# Schematic.net
KiCad netlist of a schematic drawn in EAGLE
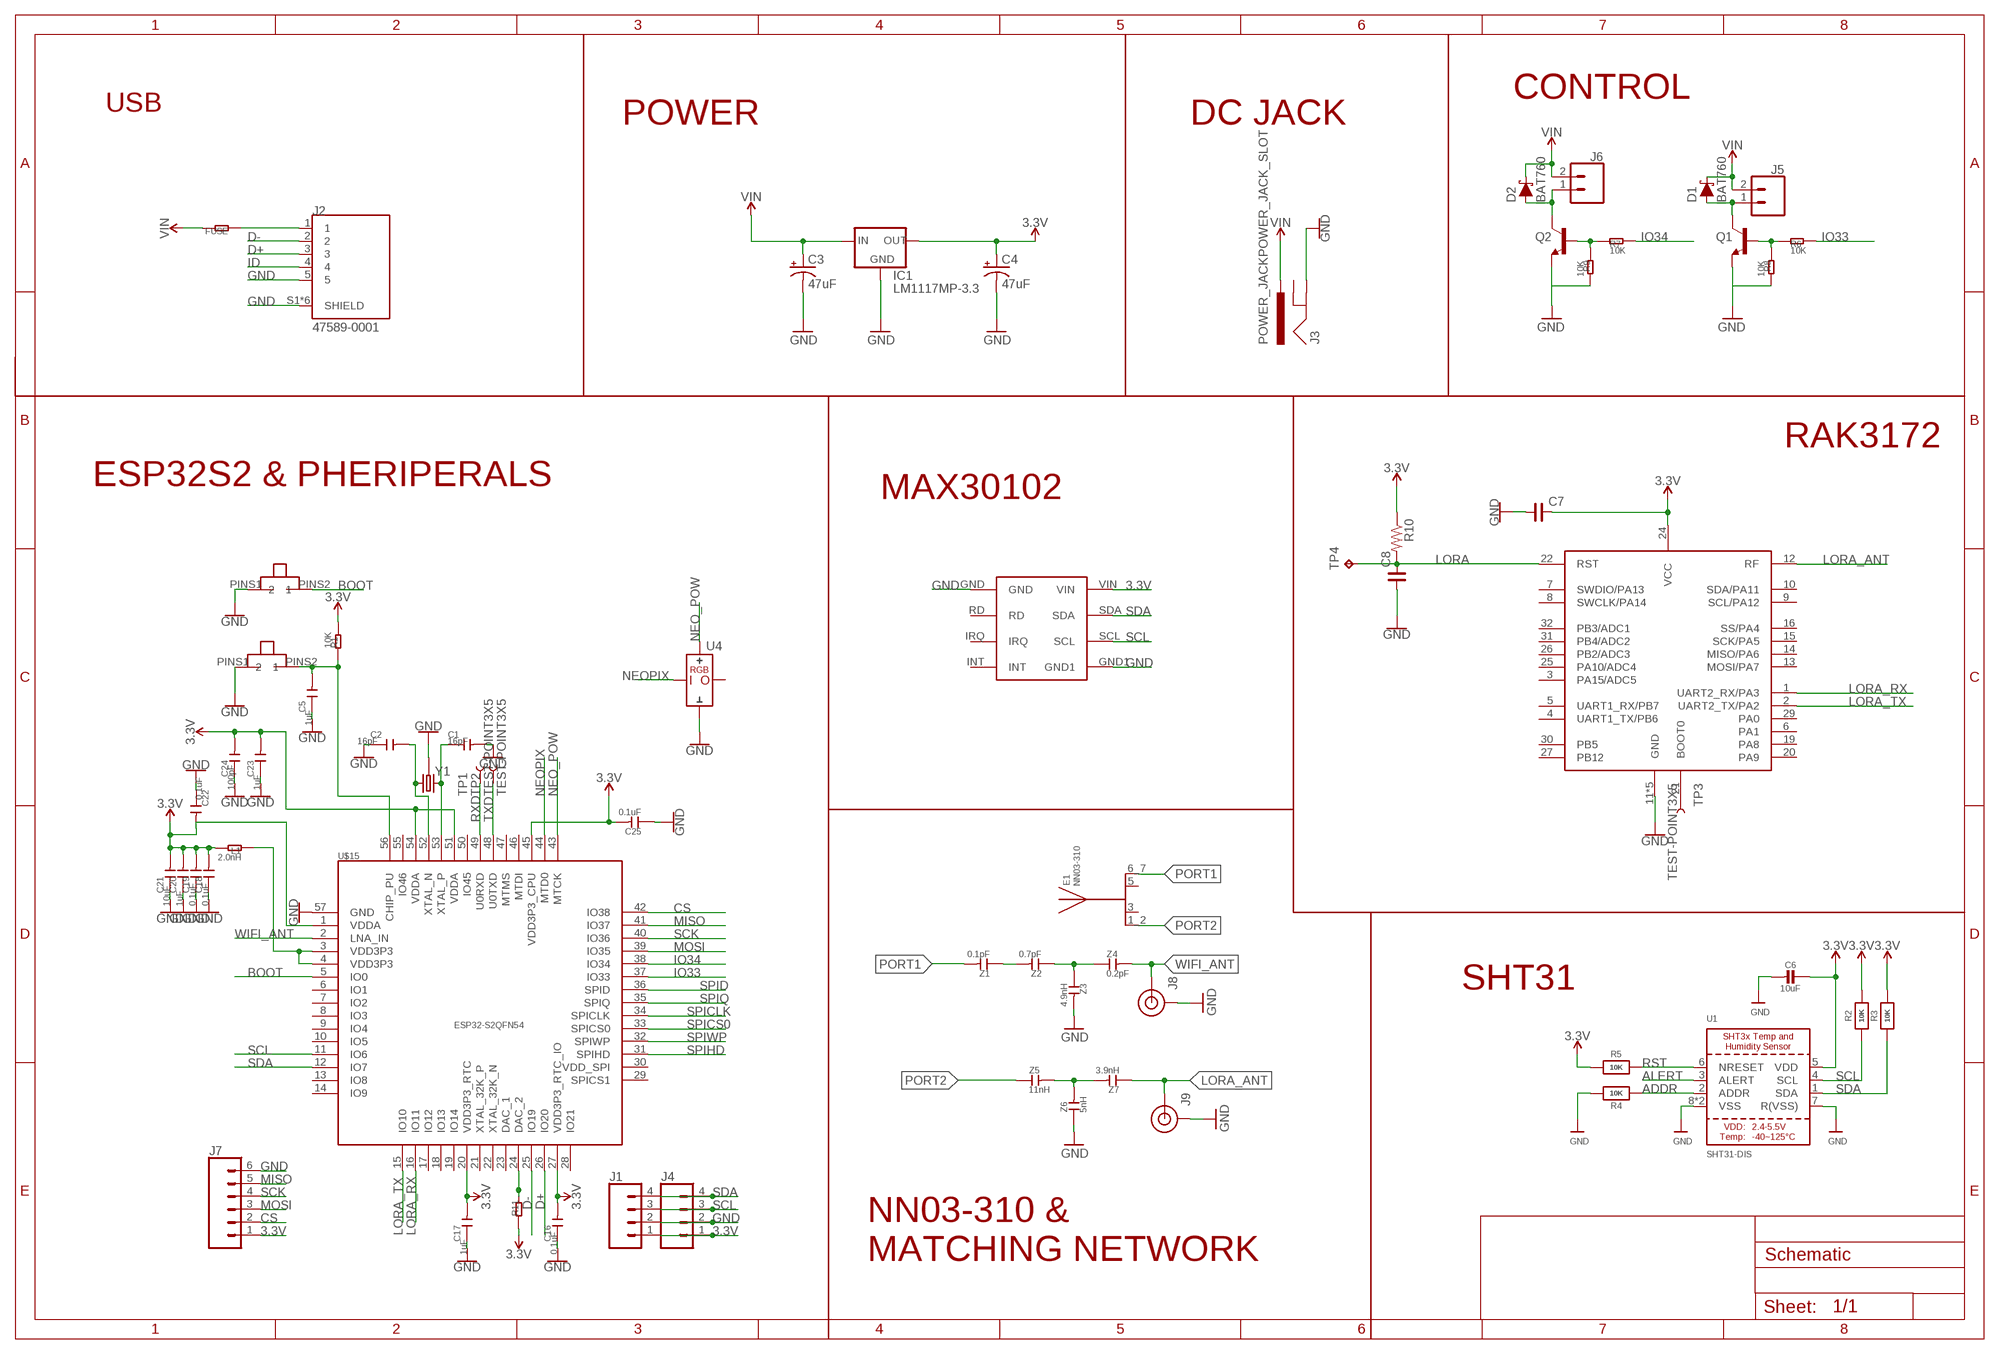
[diagram p0: schematic, sheet 1]

(export (version "E")
  (design (tool "Eeschema 10.0.6"))
  (components
    (comp (ref "C1")
      (value "16pF")
      (footprint "eagle-import:C0603")
      (libsource (lib "eagle-import") (part "CAP-0603"))
    )
    (comp (ref "C2")
      (value "16pF")
      (footprint "eagle-import:C0603")
      (libsource (lib "eagle-import") (part "CAP-0603"))
    )
    (comp (ref "C3")
      (value "47uF")
      (footprint "eagle-import:EIA3216")
      (libsource (lib "eagle-import") (part "10UF-TANT"))
    )
    (comp (ref "C4")
      (value "47uF")
      (footprint "eagle-import:EIA3216")
      (libsource (lib "eagle-import") (part "10UF-TANT"))
    )
    (comp (ref "C5")
      (value "1uF")
      (footprint "eagle-import:C0603")
      (libsource (lib "eagle-import") (part "CAP-0603"))
    )
    (comp (ref "C6")
      (value "10uF")
      (footprint "eagle-import:0805-NO")
      (libsource (lib "eagle-import") (part "CAP_CERAMIC0805-NOOUTLINE"))
    )
    (comp (ref "C7")
      (value "C_0805")
      (footprint "eagle-import:C0805")
      (libsource (lib "eagle-import") (part "C_0805"))
    )
    (comp (ref "C8")
      (value "C_0805")
      (footprint "eagle-import:C0805")
      (libsource (lib "eagle-import") (part "C_0805"))
    )
    (comp (ref "C16")
      (value "0.1uF")
      (footprint "eagle-import:C0603")
      (libsource (lib "eagle-import") (part "CAP-0603"))
    )
    (comp (ref "C17")
      (value "1uF")
      (footprint "eagle-import:C0603")
      (libsource (lib "eagle-import") (part "CAP-0603"))
    )
    (comp (ref "C18")
      (value "0.1uF")
      (footprint "eagle-import:C0603")
      (libsource (lib "eagle-import") (part "CAP-0603"))
    )
    (comp (ref "C19")
      (value "0.1uF")
      (footprint "eagle-import:C0603")
      (libsource (lib "eagle-import") (part "CAP-0603"))
    )
    (comp (ref "C20")
      (value "1uF")
      (footprint "eagle-import:C0603")
      (libsource (lib "eagle-import") (part "CAP-0603"))
    )
    (comp (ref "C21")
      (value "10uF")
      (footprint "eagle-import:C0603")
      (libsource (lib "eagle-import") (part "CAP-0603"))
    )
    (comp (ref "C22")
      (value "0.1uF")
      (footprint "eagle-import:C0603")
      (libsource (lib "eagle-import") (part "CAP-0603"))
    )
    (comp (ref "C23")
      (value "1uF")
      (footprint "eagle-import:C0603")
      (libsource (lib "eagle-import") (part "CAP-0603"))
    )
    (comp (ref "C24")
      (value "100pF")
      (footprint "eagle-import:C0603")
      (libsource (lib "eagle-import") (part "CAP-0603"))
    )
    (comp (ref "C25")
      (value "0.1uF")
      (footprint "eagle-import:C0603")
      (libsource (lib "eagle-import") (part "CAP-0603"))
    )
    (comp (ref "D1")
      (value "BAT760")
      (footprint "eagle-import:SOD-323")
      (libsource (lib "eagle-import") (part "DIODE-SCHOTTKY-BAT60A"))
    )
    (comp (ref "D2")
      (value "BAT760")
      (footprint "eagle-import:SOD-323")
      (libsource (lib "eagle-import") (part "DIODE-SCHOTTKY-BAT60A"))
    )
    (comp (ref "E1")
      (value "NN03-310")
      (footprint "eagle-import:XCVR_NN03-310")
      (fields (field (name "MF") "Ignion"))
      (libsource (lib "eagle-import") (part "NN03-310"))
    )
    (comp (ref "FUSE")
      (value "2.0K")
      (footprint "eagle-import:R0603")
      (libsource (lib "eagle-import") (part "RES-0603"))
    )
    (comp (ref "IC1")
      (value "LM1117MP-3.3")
      (footprint "eagle-import:SOT223")
      (fields (field (name "MF") "Texas Instruments"))
      (libsource (lib "eagle-import") (part "LM1117?-MP3.3"))
    )
    (comp (ref "J1")
      (value "CONN_041X04_NO_SILK")
      (footprint "eagle-import:1X04_NO_SILK")
      (libsource (lib "eagle-import") (part "CONN_041X04_NO_SILK"))
    )
    (comp (ref "J2")
      (value "47589-0001")
      (footprint "eagle-import:MOLEX_47589-0001")
      (fields (field (name "MF") "Molex"))
      (libsource (lib "eagle-import") (part "47589-0001"))
    )
    (comp (ref "J3")
      (value "POWER_JACKPOWER_JACK_SLOT")
      (footprint "eagle-import:POWER_JACK_PTH_SLOT")
      (libsource (lib "eagle-import") (part "POWER_JACKPOWER_JACK_SLOT"))
    )
    (comp (ref "J4")
      (value "CONN_041X04_NO_SILK")
      (footprint "eagle-import:1X04_NO_SILK")
      (libsource (lib "eagle-import") (part "CONN_041X04_NO_SILK"))
    )
    (comp (ref "J5")
      (value "CONN_021X02_NO_SILK")
      (footprint "eagle-import:1X02_NO_SILK")
      (libsource (lib "eagle-import") (part "CONN_021X02_NO_SILK"))
    )
    (comp (ref "J6")
      (value "CONN_021X02_NO_SILK")
      (footprint "eagle-import:1X02_NO_SILK")
      (libsource (lib "eagle-import") (part "CONN_021X02_NO_SILK"))
    )
    (comp (ref "J7")
      (value "CONN_06NO_SILK_FEMALE_PTH")
      (footprint "eagle-import:1X06_NO_SILK")
      (libsource (lib "eagle-import") (part "CONN_06NO_SILK_FEMALE_PTH"))
    )
    (comp (ref "J8")
      (value "U.FL2PIN-REDUCED-FOOTPRINT")
      (footprint "eagle-import:U.FL_REDUCED_FOOTPRINT")
      (libsource (lib "eagle-import") (part "U.FL2PIN-REDUCED-FOOTPRINT"))
    )
    (comp (ref "J9")
      (value "U.FL2PIN-REDUCED-FOOTPRINT")
      (footprint "eagle-import:U.FL_REDUCED_FOOTPRINT")
      (libsource (lib "eagle-import") (part "U.FL2PIN-REDUCED-FOOTPRINT"))
    )
    (comp (ref "L1")
      (value "2.0nH")
      (footprint "eagle-import:R0603")
      (libsource (lib "eagle-import") (part "RES-0603"))
    )
    (comp (ref "Q1")
      (value "500mA/300V")
      (footprint "eagle-import:SOT23-3")
      (libsource (lib "eagle-import") (part "TRANS_NPN-MMBTA42"))
    )
    (comp (ref "Q2")
      (value "500mA/300V")
      (footprint "eagle-import:SOT23-3")
      (libsource (lib "eagle-import") (part "TRANS_NPN-MMBTA42"))
    )
    (comp (ref "R1")
      (value "10K")
      (footprint "eagle-import:R0603")
      (libsource (lib "eagle-import") (part "RES-0603"))
    )
    (comp (ref "R2")
      (value "10K")
      (footprint "eagle-import:0805-NO")
      (libsource (lib "eagle-import") (part "RESISTOR0805_NOOUTLINE"))
    )
    (comp (ref "R3")
      (value "10K")
      (footprint "eagle-import:0805-NO")
      (libsource (lib "eagle-import") (part "RESISTOR0805_NOOUTLINE"))
    )
    (comp (ref "R4")
      (value "10K")
      (footprint "eagle-import:_0805MP")
      (libsource (lib "eagle-import") (part "RESISTOR_0805MP"))
    )
    (comp (ref "R5")
      (value "10K")
      (footprint "eagle-import:0805-NO")
      (libsource (lib "eagle-import") (part "RESISTOR0805_NOOUTLINE"))
    )
    (comp (ref "R6")
      (value "10K")
      (footprint "eagle-import:R0603")
      (libsource (lib "eagle-import") (part "RES-0603"))
    )
    (comp (ref "R7")
      (value "10K")
      (footprint "eagle-import:R0603")
      (libsource (lib "eagle-import") (part "RES-0603"))
    )
    (comp (ref "R8")
      (value "10K")
      (footprint "eagle-import:R0603")
      (libsource (lib "eagle-import") (part "RES-0603"))
    )
    (comp (ref "R9")
      (value "10K")
      (footprint "eagle-import:R0603")
      (libsource (lib "eagle-import") (part "RES-0603"))
    )
    (comp (ref "R10")
      (value "CRCW08050000Z0EA")
      (footprint "eagle-import:RES_0805")
      (fields
        (field (name "DIGIKEY_PART_NUMBER") "541-0.0ATR-ND")
        (field (name "MANUFACTURER") "Vishay Dale")
        (field (name "CREATED_BY") "PCBLayout.com")
      )
      (libsource (lib "eagle-import") (part "CRCW08050000Z0EA"))
    )
    (comp (ref "R11")
      (value "10K")
      (footprint "eagle-import:R0603")
      (libsource (lib "eagle-import") (part "RES-0603"))
    )
    (comp (ref "TP1")
      (value "TEST-POINT3X5")
      (footprint "eagle-import:PAD.03X.05")
      (libsource (lib "eagle-import") (part "TEST-POINT3X5"))
    )
    (comp (ref "TP2")
      (value "TEST-POINT3X5")
      (footprint "eagle-import:PAD.03X.05")
      (libsource (lib "eagle-import") (part "TEST-POINT3X5"))
    )
    (comp (ref "TP3")
      (value "TEST-POINT3X5")
      (footprint "eagle-import:PAD.03X.05")
      (libsource (lib "eagle-import") (part "TEST-POINT3X5"))
    )
    (comp (ref "TP4")
      (value "TPTP12R")
      (footprint "eagle-import:TP12R")
      (libsource (lib "eagle-import") (part "TPTP12R"))
    )
    (comp (ref "U$1")
      (value "TACTILE")
      (footprint "eagle-import:TACTILE")
      (libsource (lib "eagle-import") (part "TACTILE"))
    )
    (comp (ref "U$2")
      (value "TACTILE")
      (footprint "eagle-import:TACTILE")
      (libsource (lib "eagle-import") (part "TACTILE"))
    )
    (comp (ref "U$3")
      (value "MAX30102_BREAKOUT")
      (footprint "eagle-import:MAX30102")
      (libsource (lib "eagle-import") (part "MAX30102_BREAKOUT"))
    )
    (comp (ref "U$4")
      (value "RAK3172HF")
      (footprint "eagle-import:RAK3172")
      (libsource (lib "eagle-import") (part "RAK3172HF"))
    )
    (comp (ref "U$15")
      (value "ESP32-S2QFN54")
      (footprint "eagle-import:QFN40P700X700X90-57T400N")
      (fields
        (field (name "DIGI-KEY_PART_NUMBER") "1965-ESP32-S2CT-ND")
        (field (name "MF") "Espressif Systems")
        (field (name "MP") "ESP32-S2")
      )
      (libsource (lib "eagle-import") (part "ESP32-S2QFN54"))
    )
    (comp (ref "U1")
      (value "SHT31-DIS")
      (footprint "eagle-import:SHT3X")
      (libsource (lib "eagle-import") (part "SHT3X"))
    )
    (comp (ref "U4")
      (value "LED-ADDRESSABLE16MM")
      (footprint "eagle-import:LED-WS2812B-2020-RING")
      (libsource (lib "eagle-import") (part "LED-ADDRESSABLE16MM"))
    )
    (comp (ref "Y1")
      (value "CRYSTAL-GROUNDEDSMD-3.2X2.5")
      (footprint "eagle-import:CRYSTAL-SMD-3.2X2.5MM")
      (libsource (lib "eagle-import") (part "CRYSTAL-GROUNDEDSMD-3.2X2.5"))
    )
    (comp (ref "Z1")
      (value "0.1pF")
      (footprint "eagle-import:C0603")
      (libsource (lib "eagle-import") (part "CAP-0603"))
    )
    (comp (ref "Z2")
      (value "0.7pF")
      (footprint "eagle-import:C0603")
      (libsource (lib "eagle-import") (part "CAP-0603"))
    )
    (comp (ref "Z3")
      (value "4.9nH")
      (footprint "eagle-import:C0603")
      (libsource (lib "eagle-import") (part "CAP-0603"))
    )
    (comp (ref "Z4")
      (value "0.2pF")
      (footprint "eagle-import:C0603")
      (libsource (lib "eagle-import") (part "CAP-0603"))
    )
    (comp (ref "Z5")
      (value "11nH")
      (footprint "eagle-import:C0603")
      (libsource (lib "eagle-import") (part "CAP-0603"))
    )
    (comp (ref "Z6")
      (value "5nH")
      (footprint "eagle-import:C0603")
      (libsource (lib "eagle-import") (part "CAP-0603"))
    )
    (comp (ref "Z7")
      (value "3.9nH")
      (footprint "eagle-import:C0603")
      (libsource (lib "eagle-import") (part "CAP-0603"))
    )
  )
  (nets
    (net (code "1") (name "/ADDR") (class "Default")
      (node (ref "R4") (pin "1") (pinfunction "1_1") (pintype "passive"))
      (node (ref "U1") (pin "2") (pinfunction "ADDR_2") (pintype "bidirectional"))
    )
    (net (code "2") (name "/ALERT") (class "Default")
      (node (ref "U1") (pin "3") (pinfunction "ALERT_3") (pintype "bidirectional"))
    )
    (net (code "3") (name "/BOOT") (class "Default")
      (node (ref "U$15") (pin "5") (pinfunction "IO0_5") (pintype "bidirectional"))
      (node (ref "U$2") (pin "PINS2") (pinfunction "2_PINS2") (pintype "bidirectional"))
    )
    (net (code "4") (name "/CS") (class "Default")
      (node (ref "J7") (pin "2") (pinfunction "2_2") (pintype "passive"))
      (node (ref "U$15") (pin "42") (pinfunction "IO38_42") (pintype "bidirectional"))
    )
    (net (code "5") (name "/D+") (class "Default")
      (node (ref "J2") (pin "3") (pinfunction "3_3") (pintype "passive"))
      (node (ref "U$15") (pin "26") (pinfunction "IO20_26") (pintype "bidirectional"))
    )
    (net (code "6") (name "/D-") (class "Default")
      (node (ref "J2") (pin "2") (pinfunction "2_2") (pintype "passive"))
      (node (ref "U$15") (pin "25") (pinfunction "IO19_25") (pintype "bidirectional"))
    )
    (net (code "7") (name "/ID") (class "Default")
      (node (ref "J2") (pin "4") (pinfunction "4_4") (pintype "passive"))
    )
    (net (code "8") (name "/IO33") (class "Default")
      (node (ref "R6") (pin "2") (pinfunction "2_2") (pintype "passive"))
      (node (ref "U$15") (pin "37") (pinfunction "IO33_37") (pintype "bidirectional"))
    )
    (net (code "9") (name "/IO34") (class "Default")
      (node (ref "R7") (pin "2") (pinfunction "2_2") (pintype "passive"))
      (node (ref "U$15") (pin "38") (pinfunction "IO34_38") (pintype "bidirectional"))
    )
    (net (code "10") (name "/LORA") (class "Default")
      (node (ref "C8") (pin "2") (pinfunction "2_2") (pintype "passive"))
      (node (ref "R10") (pin "2") (pinfunction "2_2") (pintype "passive"))
      (node (ref "TP4") (pin "TP") (pinfunction "TP_TP") (pintype "input"))
      (node (ref "U$4") (pin "22") (pinfunction "RST_22") (pintype "input"))
    )
    (net (code "11") (name "/LORA_RX") (class "Default")
      (node (ref "U$15") (pin "16") (pinfunction "IO11_16") (pintype "bidirectional"))
      (node (ref "U$4") (pin "1") (pinfunction "UART2_RX/PA3_1") (pintype "bidirectional"))
    )
    (net (code "12") (name "/LORA_TX") (class "Default")
      (node (ref "U$15") (pin "15") (pinfunction "IO10_15") (pintype "bidirectional"))
      (node (ref "U$4") (pin "2") (pinfunction "UART2_TX/PA2_2") (pintype "bidirectional"))
    )
    (net (code "13") (name "/MISO") (class "Default")
      (node (ref "J7") (pin "5") (pinfunction "5_5") (pintype "passive"))
      (node (ref "U$15") (pin "41") (pinfunction "IO37_41") (pintype "bidirectional"))
    )
    (net (code "14") (name "/MOSI") (class "Default")
      (node (ref "J7") (pin "3") (pinfunction "3_3") (pintype "passive"))
      (node (ref "U$15") (pin "39") (pinfunction "IO35_39") (pintype "bidirectional"))
    )
    (net (code "15") (name "/NEOPIX") (class "Default")
      (node (ref "U$15") (pin "44") (pinfunction "MTD0_44") (pintype "bidirectional"))
      (node (ref "U4") (pin "DI") (pinfunction "DI_DI") (pintype "bidirectional"))
    )
    (net (code "16") (name "/NEO_POW") (class "Default")
      (node (ref "U$15") (pin "43") (pinfunction "MTCK_43") (pintype "bidirectional"))
      (node (ref "U4") (pin "+") (pinfunction "VDD_+") (pintype "bidirectional"))
    )
    (net (code "17") (name "/RST") (class "Default")
      (node (ref "R5") (pin "2") (pinfunction "2_2") (pintype "passive"))
      (node (ref "U1") (pin "6") (pinfunction "NRESET_6") (pintype "bidirectional"))
    )
    (net (code "18") (name "/RXD") (class "Default")
      (node (ref "TP1") (pin "P$1") (pinfunction "1_P$1") (pintype "bidirectional"))
      (node (ref "U$15") (pin "49") (pinfunction "U0RXD_49") (pintype "bidirectional"))
    )
    (net (code "19") (name "/SCK") (class "Default")
      (node (ref "J7") (pin "4") (pinfunction "4_4") (pintype "passive"))
      (node (ref "U$15") (pin "40") (pinfunction "IO36_40") (pintype "bidirectional"))
    )
    (net (code "20") (name "/SCL") (class "Default")
      (node (ref "J1") (pin "3") (pinfunction "3_3") (pintype "passive"))
      (node (ref "J4") (pin "3") (pinfunction "3_3") (pintype "passive"))
      (node (ref "R2") (pin "1") (pinfunction "1_1") (pintype "passive"))
      (node (ref "U$15") (pin "11") (pinfunction "IO6_11") (pintype "bidirectional"))
      (node (ref "U$3") (pin "SCL") (pinfunction "SCL_SCL") (pintype "bidirectional"))
      (node (ref "U1") (pin "4") (pinfunction "SCL_4") (pintype "bidirectional"))
    )
    (net (code "21") (name "/SDA") (class "Default")
      (node (ref "J1") (pin "4") (pinfunction "4_4") (pintype "passive"))
      (node (ref "J4") (pin "4") (pinfunction "4_4") (pintype "passive"))
      (node (ref "R3") (pin "1") (pinfunction "1_1") (pintype "passive"))
      (node (ref "U$15") (pin "12") (pinfunction "IO7_12") (pintype "bidirectional"))
      (node (ref "U$3") (pin "SDA") (pinfunction "SDA_SDA") (pintype "bidirectional"))
      (node (ref "U1") (pin "1") (pinfunction "SDA_1") (pintype "bidirectional"))
    )
    (net (code "22") (name "/SPICLK") (class "Default")
      (node (ref "U$15") (pin "34") (pinfunction "SPICLK_34") (pintype "bidirectional"))
    )
    (net (code "23") (name "/SPICS0") (class "Default")
      (node (ref "U$15") (pin "33") (pinfunction "SPICS0_33") (pintype "bidirectional"))
    )
    (net (code "24") (name "/SPID") (class "Default")
      (node (ref "U$15") (pin "36") (pinfunction "SPID_36") (pintype "bidirectional"))
    )
    (net (code "25") (name "/SPIHD") (class "Default")
      (node (ref "U$15") (pin "31") (pinfunction "SPIHD_31") (pintype "bidirectional"))
    )
    (net (code "26") (name "/SPIQ") (class "Default")
      (node (ref "U$15") (pin "35") (pinfunction "SPIQ_35") (pintype "bidirectional"))
    )
    (net (code "27") (name "/SPIWP") (class "Default")
      (node (ref "U$15") (pin "32") (pinfunction "SPIWP_32") (pintype "bidirectional"))
    )
    (net (code "28") (name "/TXD") (class "Default")
      (node (ref "TP2") (pin "P$1") (pinfunction "1_P$1") (pintype "bidirectional"))
      (node (ref "U$15") (pin "48") (pinfunction "U0TXD_48") (pintype "bidirectional"))
    )
    (net (code "29") (name "/VDD_SPI") (class "Default")
      (node (ref "U$15") (pin "30") (pinfunction "VDD_SPI_30") (pintype "power_in"))
    )
    (net (code "30") (name "3.3V") (class "Default")
      (node (ref "C16") (pin "2") (pinfunction "2_2") (pintype "passive"))
      (node (ref "C17") (pin "2") (pinfunction "2_2") (pintype "passive"))
      (node (ref "C18") (pin "2") (pinfunction "2_2") (pintype "passive"))
      (node (ref "C19") (pin "2") (pinfunction "2_2") (pintype "passive"))
      (node (ref "C20") (pin "2") (pinfunction "2_2") (pintype "passive"))
      (node (ref "C21") (pin "2") (pinfunction "2_2") (pintype "passive"))
      (node (ref "C22") (pin "2") (pinfunction "2_2") (pintype "passive"))
      (node (ref "C23") (pin "2") (pinfunction "2_2") (pintype "passive"))
      (node (ref "C24") (pin "2") (pinfunction "2_2") (pintype "passive"))
      (node (ref "C25") (pin "2") (pinfunction "2_2") (pintype "passive"))
      (node (ref "C4") (pin "A") (pinfunction "+_A") (pintype "passive"))
      (node (ref "C6") (pin "1") (pinfunction "1_1") (pintype "passive"))
      (node (ref "C7") (pin "2") (pinfunction "2_2") (pintype "passive"))
      (node (ref "IC1") (pin "2") (pinfunction "OUT_2") (pintype "passive"))
      (node (ref "IC1") (pin "4") (pinfunction "OUT_4") (pintype "passive"))
      (node (ref "J1") (pin "1") (pinfunction "1_1") (pintype "passive"))
      (node (ref "J4") (pin "1") (pinfunction "1_1") (pintype "passive"))
      (node (ref "J7") (pin "1") (pinfunction "1_1") (pintype "passive"))
      (node (ref "L1") (pin "2") (pinfunction "2_2") (pintype "passive"))
      (node (ref "R1") (pin "2") (pinfunction "2_2") (pintype "passive"))
      (node (ref "R10") (pin "1") (pinfunction "1_1") (pintype "passive"))
      (node (ref "R11") (pin "1") (pinfunction "1_1") (pintype "passive"))
      (node (ref "R2") (pin "2") (pinfunction "2_2") (pintype "passive"))
      (node (ref "R3") (pin "2") (pinfunction "2_2") (pintype "passive"))
      (node (ref "R5") (pin "1") (pinfunction "1_1") (pintype "passive"))
      (node (ref "U$15") (pin "1") (pinfunction "VDDA_1") (pintype "power_in"))
      (node (ref "U$15") (pin "20") (pinfunction "VDD3P3_RTC_20") (pintype "power_in"))
      (node (ref "U$15") (pin "27") (pinfunction "VDD3P3_RTC_IO_27") (pintype "power_in"))
      (node (ref "U$15") (pin "45") (pinfunction "VDD3P3_CPU_45") (pintype "power_in"))
      (node (ref "U$15") (pin "51") (pinfunction "VDDA_51") (pintype "power_in"))
      (node (ref "U$15") (pin "54") (pinfunction "VDDA_54") (pintype "power_in"))
      (node (ref "U$3") (pin "VIN") (pinfunction "VIN_VIN") (pintype "bidirectional"))
      (node (ref "U$4") (pin "24") (pinfunction "VCC_24") (pintype "power_in"))
      (node (ref "U1") (pin "5") (pinfunction "VDD_5") (pintype "power_in"))
    )
    (net (code "31") (name "GND") (class "Default")
      (node (ref "C1") (pin "2") (pinfunction "2_2") (pintype "passive"))
      (node (ref "C16") (pin "1") (pinfunction "1_1") (pintype "passive"))
      (node (ref "C17") (pin "1") (pinfunction "1_1") (pintype "passive"))
      (node (ref "C18") (pin "1") (pinfunction "1_1") (pintype "passive"))
      (node (ref "C19") (pin "1") (pinfunction "1_1") (pintype "passive"))
      (node (ref "C2") (pin "1") (pinfunction "1_1") (pintype "passive"))
      (node (ref "C20") (pin "1") (pinfunction "1_1") (pintype "passive"))
      (node (ref "C21") (pin "1") (pinfunction "1_1") (pintype "passive"))
      (node (ref "C22") (pin "1") (pinfunction "1_1") (pintype "passive"))
      (node (ref "C23") (pin "1") (pinfunction "1_1") (pintype "passive"))
      (node (ref "C24") (pin "1") (pinfunction "1_1") (pintype "passive"))
      (node (ref "C25") (pin "1") (pinfunction "1_1") (pintype "passive"))
      (node (ref "C3") (pin "C") (pinfunction "-_C") (pintype "passive"))
      (node (ref "C4") (pin "C") (pinfunction "-_C") (pintype "passive"))
      (node (ref "C5") (pin "1") (pinfunction "1_1") (pintype "passive"))
      (node (ref "C6") (pin "2") (pinfunction "2_2") (pintype "passive"))
      (node (ref "C7") (pin "1") (pinfunction "1_1") (pintype "passive"))
      (node (ref "C8") (pin "1") (pinfunction "1_1") (pintype "passive"))
      (node (ref "IC1") (pin "1") (pinfunction "GND_1") (pintype "input"))
      (node (ref "J1") (pin "2") (pinfunction "2_2") (pintype "passive"))
      (node (ref "J2") (pin "5") (pinfunction "5_5") (pintype "passive"))
      (node (ref "J2") (pin "S1") (pinfunction "SHIELD_S1") (pintype "passive"))
      (node (ref "J2") (pin "S2") (pinfunction "SHIELD_S2") (pintype "passive"))
      (node (ref "J2") (pin "S3") (pinfunction "SHIELD_S3") (pintype "passive"))
      (node (ref "J2") (pin "S4") (pinfunction "SHIELD_S4") (pintype "passive"))
      (node (ref "J2") (pin "S5") (pinfunction "SHIELD_S5") (pintype "passive"))
      (node (ref "J2") (pin "S6") (pinfunction "SHIELD_S6") (pintype "passive"))
      (node (ref "J3") (pin "GND") (pinfunction "GND_GND") (pintype "bidirectional"))
      (node (ref "J4") (pin "2") (pinfunction "2_2") (pintype "passive"))
      (node (ref "J7") (pin "6") (pinfunction "6_6") (pintype "passive"))
      (node (ref "J8") (pin "1") (pinfunction "GND_1") (pintype "bidirectional"))
      (node (ref "J8") (pin "2") (pinfunction "GND_2") (pintype "bidirectional"))
      (node (ref "J9") (pin "1") (pinfunction "GND_1") (pintype "bidirectional"))
      (node (ref "J9") (pin "2") (pinfunction "GND_2") (pintype "bidirectional"))
      (node (ref "Q1") (pin "2") (pinfunction "E_2") (pintype "passive"))
      (node (ref "Q2") (pin "2") (pinfunction "E_2") (pintype "passive"))
      (node (ref "R4") (pin "2") (pinfunction "2_2") (pintype "passive"))
      (node (ref "R8") (pin "2") (pinfunction "2_2") (pintype "passive"))
      (node (ref "R9") (pin "2") (pinfunction "2_2") (pintype "passive"))
      (node (ref "U$1") (pin "PINS1") (pinfunction "1_PINS1") (pintype "bidirectional"))
      (node (ref "U$15") (pin "57") (pinfunction "GND_57") (pintype "power_in"))
      (node (ref "U$2") (pin "PINS1") (pinfunction "1_PINS1") (pintype "bidirectional"))
      (node (ref "U$3") (pin "GND") (pinfunction "GND_GND") (pintype "bidirectional"))
      (node (ref "U$3") (pin "GND1") (pinfunction "GND1_GND1") (pintype "bidirectional"))
      (node (ref "U$4") (pin "11") (pinfunction "GND_11") (pintype "power_in"))
      (node (ref "U$4") (pin "17") (pinfunction "GND_17") (pintype "power_in"))
      (node (ref "U$4") (pin "18") (pinfunction "GND_18") (pintype "power_in"))
      (node (ref "U$4") (pin "23") (pinfunction "GND_23") (pintype "power_in"))
      (node (ref "U$4") (pin "28") (pinfunction "GND_28") (pintype "power_in"))
      (node (ref "U1") (pin "7") (pinfunction "R(VSS)_7") (pintype "bidirectional"))
      (node (ref "U1") (pin "8") (pinfunction "VSS_8") (pintype "power_in"))
      (node (ref "U1") (pin "THERMAL") (pinfunction "VSS_THERMAL") (pintype "power_in"))
      (node (ref "U4") (pin "GND") (pinfunction "GND_GND") (pintype "bidirectional"))
      (node (ref "Y1") (pin "2") (pinfunction "GND_2") (pintype "power_in"))
      (node (ref "Y1") (pin "4") (pinfunction "GND_4") (pintype "power_in"))
      (node (ref "Z3") (pin "2") (pinfunction "2_2") (pintype "passive"))
      (node (ref "Z6") (pin "1") (pinfunction "1_1") (pintype "passive"))
    )
    (net (code "32") (name "LORA_ANT") (class "Default")
      (node (ref "J9") (pin "FEED") (pinfunction "SIGNAL_FEED") (pintype "bidirectional"))
      (node (ref "U$4") (pin "12") (pinfunction "RF_12") (pintype "output"))
      (node (ref "Z7") (pin "1") (pinfunction "1_1") (pintype "passive"))
    )
    (net (code "33") (name "Net-(FUSE-Pad1)") (class "Default")
      (node (ref "FUSE") (pin "1") (pinfunction "1_1") (pintype "passive"))
      (node (ref "J2") (pin "1") (pinfunction "1_1") (pintype "passive"))
    )
    (net (code "34") (name "Net-(L1-Pad1)") (class "Default")
      (node (ref "L1") (pin "1") (pinfunction "1_1") (pintype "passive"))
      (node (ref "U$15") (pin "3") (pinfunction "VDD3P3_3") (pintype "power_in"))
      (node (ref "U$15") (pin "4") (pinfunction "VDD3P3_4") (pintype "power_in"))
    )
    (net (code "35") (name "Net-(Q1-B)") (class "Default")
      (node (ref "Q1") (pin "1") (pinfunction "B_1") (pintype "passive"))
      (node (ref "R6") (pin "1") (pinfunction "1_1") (pintype "passive"))
      (node (ref "R8") (pin "1") (pinfunction "1_1") (pintype "passive"))
    )
    (net (code "36") (name "Net-(Q1-C)") (class "Default")
      (node (ref "D1") (pin "A") (pinfunction "A_A") (pintype "passive"))
      (node (ref "J5") (pin "1") (pinfunction "1_1") (pintype "passive"))
      (node (ref "Q1") (pin "3") (pinfunction "C_3") (pintype "passive"))
    )
    (net (code "37") (name "Net-(Q2-B)") (class "Default")
      (node (ref "Q2") (pin "1") (pinfunction "B_1") (pintype "passive"))
      (node (ref "R7") (pin "1") (pinfunction "1_1") (pintype "passive"))
      (node (ref "R9") (pin "1") (pinfunction "1_1") (pintype "passive"))
    )
    (net (code "38") (name "Net-(Q2-C)") (class "Default")
      (node (ref "D2") (pin "A") (pinfunction "A_A") (pintype "passive"))
      (node (ref "J6") (pin "1") (pinfunction "1_1") (pintype "passive"))
      (node (ref "Q2") (pin "3") (pinfunction "C_3") (pintype "passive"))
    )
    (net (code "39") (name "Net-(TP3-1)") (class "Default")
      (node (ref "TP3") (pin "P$1") (pinfunction "1_P$1") (pintype "bidirectional"))
      (node (ref "U$4") (pin "21") (pinfunction "BOOT0_21") (pintype "input"))
    )
    (net (code "40") (name "Net-(U$1-2)") (class "Default")
      (node (ref "C5") (pin "2") (pinfunction "2_2") (pintype "passive"))
      (node (ref "R1") (pin "1") (pinfunction "1_1") (pintype "passive"))
      (node (ref "U$1") (pin "PINS2") (pinfunction "2_PINS2") (pintype "bidirectional"))
      (node (ref "U$15") (pin "56") (pinfunction "CHIP_PU_56") (pintype "input"))
    )
    (net (code "41") (name "Net-(U$15-DAC_2)") (class "Default")
      (node (ref "R11") (pin "2") (pinfunction "2_2") (pintype "passive"))
      (node (ref "U$15") (pin "24") (pinfunction "DAC_2_24") (pintype "bidirectional"))
    )
    (net (code "42") (name "Net-(U$15-XTAL_N)") (class "Default")
      (node (ref "C2") (pin "2") (pinfunction "2_2") (pintype "passive"))
      (node (ref "U$15") (pin "52") (pinfunction "XTAL_N_52") (pintype "bidirectional"))
      (node (ref "Y1") (pin "3") (pinfunction "2_3") (pintype "passive"))
    )
    (net (code "43") (name "Net-(U$15-XTAL_P)") (class "Default")
      (node (ref "C1") (pin "1") (pinfunction "1_1") (pintype "passive"))
      (node (ref "U$15") (pin "53") (pinfunction "XTAL_P_53") (pintype "bidirectional"))
      (node (ref "Y1") (pin "1") (pinfunction "1_1") (pintype "passive"))
    )
    (net (code "44") (name "Net-(Z1-Pad1)") (class "Default")
      (node (ref "Z1") (pin "1") (pinfunction "1_1") (pintype "passive"))
      (node (ref "Z2") (pin "2") (pinfunction "2_2") (pintype "passive"))
    )
    (net (code "45") (name "Net-(Z2-Pad1)") (class "Default")
      (node (ref "Z2") (pin "1") (pinfunction "1_1") (pintype "passive"))
      (node (ref "Z3") (pin "1") (pinfunction "1_1") (pintype "passive"))
      (node (ref "Z4") (pin "1") (pinfunction "1_1") (pintype "passive"))
    )
    (net (code "46") (name "Net-(Z5-Pad2)") (class "Default")
      (node (ref "Z5") (pin "2") (pinfunction "2_2") (pintype "passive"))
      (node (ref "Z6") (pin "2") (pinfunction "2_2") (pintype "passive"))
      (node (ref "Z7") (pin "2") (pinfunction "2_2") (pintype "passive"))
    )
    (net (code "47") (name "PORT1") (class "Default")
      (node (ref "E1") (pin "6_7") (pinfunction "6_6_7") (pintype "passive"))
      (node (ref "Z1") (pin "2") (pinfunction "2_2") (pintype "passive"))
    )
    (net (code "48") (name "PORT2") (class "Default")
      (node (ref "E1") (pin "1_2") (pinfunction "1_1_2") (pintype "input"))
      (node (ref "Z5") (pin "1") (pinfunction "1_1") (pintype "passive"))
    )
    (net (code "49") (name "VIN") (class "Default")
      (node (ref "C3") (pin "A") (pinfunction "+_A") (pintype "passive"))
      (node (ref "D1") (pin "C") (pinfunction "C_C") (pintype "passive"))
      (node (ref "D2") (pin "C") (pinfunction "C_C") (pintype "passive"))
      (node (ref "FUSE") (pin "2") (pinfunction "2_2") (pintype "passive"))
      (node (ref "IC1") (pin "3") (pinfunction "IN_3") (pintype "input"))
      (node (ref "J3") (pin "PWR") (pinfunction "PWR_PWR") (pintype "bidirectional"))
      (node (ref "J5") (pin "2") (pinfunction "2_2") (pintype "passive"))
      (node (ref "J6") (pin "2") (pinfunction "2_2") (pintype "passive"))
    )
    (net (code "50") (name "WIFI_ANT") (class "Default")
      (node (ref "J8") (pin "FEED") (pinfunction "SIGNAL_FEED") (pintype "bidirectional"))
      (node (ref "U$15") (pin "2") (pinfunction "LNA_IN_2") (pintype "bidirectional"))
      (node (ref "Z4") (pin "2") (pinfunction "2_2") (pintype "passive"))
    )
    (net (code "51") (name "unconnected-(E1-Pad3)") (class "Default")
      (node (ref "E1") (pin "3") (pinfunction "3_3") (pintype "passive"))
    )
    (net (code "52") (name "unconnected-(E1-Pad5)") (class "Default")
      (node (ref "E1") (pin "5") (pinfunction "5_5") (pintype "passive"))
    )
    (net (code "53") (name "unconnected-(J3-PadGNDBREAK)") (class "Default")
      (node (ref "J3") (pin "GNDBREAK") (pinfunction "GNDBREAK_GNDBREAK") (pintype "bidirectional"))
    )
    (net (code "54") (name "unconnected-(U$3-PadINT)") (class "Default")
      (node (ref "U$3") (pin "INT") (pinfunction "INT_INT") (pintype "bidirectional"))
    )
    (net (code "55") (name "unconnected-(U$3-PadIRQ)") (class "Default")
      (node (ref "U$3") (pin "IRQ") (pinfunction "IRQ_IRQ") (pintype "bidirectional"))
    )
    (net (code "56") (name "unconnected-(U$3-PadRD)") (class "Default")
      (node (ref "U$3") (pin "RD") (pinfunction "RD_RD") (pintype "bidirectional"))
    )
    (net (code "57") (name "unconnected-(U$4-MISO{slash}PA6-Pad14)") (class "Default")
      (node (ref "U$4") (pin "14") (pinfunction "MISO/PA6_14") (pintype "bidirectional"))
    )
    (net (code "58") (name "unconnected-(U$4-MOSI{slash}PA7-Pad13)") (class "Default")
      (node (ref "U$4") (pin "13") (pinfunction "MOSI/PA7_13") (pintype "bidirectional"))
    )
    (net (code "59") (name "unconnected-(U$4-PA0-Pad29)") (class "Default")
      (node (ref "U$4") (pin "29") (pinfunction "PA0_29") (pintype "bidirectional"))
    )
    (net (code "60") (name "unconnected-(U$4-PA1-Pad6)") (class "Default")
      (node (ref "U$4") (pin "6") (pinfunction "PA1_6") (pintype "bidirectional"))
    )
    (net (code "61") (name "unconnected-(U$4-PA8-Pad19)") (class "Default")
      (node (ref "U$4") (pin "19") (pinfunction "PA8_19") (pintype "bidirectional"))
    )
    (net (code "62") (name "unconnected-(U$4-PA9-Pad20)") (class "Default")
      (node (ref "U$4") (pin "20") (pinfunction "PA9_20") (pintype "bidirectional"))
    )
    (net (code "63") (name "unconnected-(U$4-PA10{slash}ADC4-Pad25)") (class "Default")
      (node (ref "U$4") (pin "25") (pinfunction "PA10/ADC4_25") (pintype "bidirectional"))
    )
    (net (code "64") (name "unconnected-(U$4-PA15{slash}ADC5-Pad3)") (class "Default")
      (node (ref "U$4") (pin "3") (pinfunction "PA15/ADC5_3") (pintype "bidirectional"))
    )
    (net (code "65") (name "unconnected-(U$4-PB2{slash}ADC3-Pad26)") (class "Default")
      (node (ref "U$4") (pin "26") (pinfunction "PB2/ADC3_26") (pintype "bidirectional"))
    )
    (net (code "66") (name "unconnected-(U$4-PB3{slash}ADC1-Pad32)") (class "Default")
      (node (ref "U$4") (pin "32") (pinfunction "PB3/ADC1_32") (pintype "bidirectional"))
    )
    (net (code "67") (name "unconnected-(U$4-PB4{slash}ADC2-Pad31)") (class "Default")
      (node (ref "U$4") (pin "31") (pinfunction "PB4/ADC2_31") (pintype "bidirectional"))
    )
    (net (code "68") (name "unconnected-(U$4-PB5-Pad30)") (class "Default")
      (node (ref "U$4") (pin "30") (pinfunction "PB5_30") (pintype "bidirectional"))
    )
    (net (code "69") (name "unconnected-(U$4-PB12-Pad27)") (class "Default")
      (node (ref "U$4") (pin "27") (pinfunction "PB12_27") (pintype "bidirectional"))
    )
    (net (code "70") (name "unconnected-(U$4-SCK{slash}PA5-Pad15)") (class "Default")
      (node (ref "U$4") (pin "15") (pinfunction "SCK/PA5_15") (pintype "bidirectional"))
    )
    (net (code "71") (name "unconnected-(U$4-SCL{slash}PA12-Pad9)") (class "Default")
      (node (ref "U$4") (pin "9") (pinfunction "SCL/PA12_9") (pintype "bidirectional"))
    )
    (net (code "72") (name "unconnected-(U$4-SDA{slash}PA11-Pad10)") (class "Default")
      (node (ref "U$4") (pin "10") (pinfunction "SDA/PA11_10") (pintype "bidirectional"))
    )
    (net (code "73") (name "unconnected-(U$4-SS{slash}PA4-Pad16)") (class "Default")
      (node (ref "U$4") (pin "16") (pinfunction "SS/PA4_16") (pintype "bidirectional"))
    )
    (net (code "74") (name "unconnected-(U$4-SWCLK{slash}PA14-Pad8)") (class "Default")
      (node (ref "U$4") (pin "8") (pinfunction "SWCLK/PA14_8") (pintype "bidirectional"))
    )
    (net (code "75") (name "unconnected-(U$4-SWDIO{slash}PA13-Pad7)") (class "Default")
      (node (ref "U$4") (pin "7") (pinfunction "SWDIO/PA13_7") (pintype "bidirectional"))
    )
    (net (code "76") (name "unconnected-(U$4-UART1_RX{slash}PB7-Pad5)") (class "Default")
      (node (ref "U$4") (pin "5") (pinfunction "UART1_RX/PB7_5") (pintype "bidirectional"))
    )
    (net (code "77") (name "unconnected-(U$4-UART1_TX{slash}PB6-Pad4)") (class "Default")
      (node (ref "U$4") (pin "4") (pinfunction "UART1_TX/PB6_4") (pintype "bidirectional"))
    )
    (net (code "78") (name "unconnected-(U$15-DAC_1-Pad23)") (class "Default")
      (node (ref "U$15") (pin "23") (pinfunction "DAC_1_23") (pintype "bidirectional"))
    )
    (net (code "79") (name "unconnected-(U$15-IO1-Pad6)") (class "Default")
      (node (ref "U$15") (pin "6") (pinfunction "IO1_6") (pintype "bidirectional"))
    )
    (net (code "80") (name "unconnected-(U$15-IO2-Pad7)") (class "Default")
      (node (ref "U$15") (pin "7") (pinfunction "IO2_7") (pintype "bidirectional"))
    )
    (net (code "81") (name "unconnected-(U$15-IO3-Pad8)") (class "Default")
      (node (ref "U$15") (pin "8") (pinfunction "IO3_8") (pintype "bidirectional"))
    )
    (net (code "82") (name "unconnected-(U$15-IO4-Pad9)") (class "Default")
      (node (ref "U$15") (pin "9") (pinfunction "IO4_9") (pintype "bidirectional"))
    )
    (net (code "83") (name "unconnected-(U$15-IO5-Pad10)") (class "Default")
      (node (ref "U$15") (pin "10") (pinfunction "IO5_10") (pintype "bidirectional"))
    )
    (net (code "84") (name "unconnected-(U$15-IO8-Pad13)") (class "Default")
      (node (ref "U$15") (pin "13") (pinfunction "IO8_13") (pintype "bidirectional"))
    )
    (net (code "85") (name "unconnected-(U$15-IO9-Pad14)") (class "Default")
      (node (ref "U$15") (pin "14") (pinfunction "IO9_14") (pintype "bidirectional"))
    )
    (net (code "86") (name "unconnected-(U$15-IO12-Pad17)") (class "Default")
      (node (ref "U$15") (pin "17") (pinfunction "IO12_17") (pintype "bidirectional"))
    )
    (net (code "87") (name "unconnected-(U$15-IO13-Pad18)") (class "Default")
      (node (ref "U$15") (pin "18") (pinfunction "IO13_18") (pintype "bidirectional"))
    )
    (net (code "88") (name "unconnected-(U$15-IO14-Pad19)") (class "Default")
      (node (ref "U$15") (pin "19") (pinfunction "IO14_19") (pintype "bidirectional"))
    )
    (net (code "89") (name "unconnected-(U$15-IO21-Pad28)") (class "Default")
      (node (ref "U$15") (pin "28") (pinfunction "IO21_28") (pintype "bidirectional"))
    )
    (net (code "90") (name "unconnected-(U$15-IO45-Pad50)") (class "Default")
      (node (ref "U$15") (pin "50") (pinfunction "IO45_50") (pintype "bidirectional"))
    )
    (net (code "91") (name "unconnected-(U$15-IO46-Pad55)") (class "Default")
      (node (ref "U$15") (pin "55") (pinfunction "IO46_55") (pintype "input"))
    )
    (net (code "92") (name "unconnected-(U$15-MTDI-Pad46)") (class "Default")
      (node (ref "U$15") (pin "46") (pinfunction "MTDI_46") (pintype "bidirectional"))
    )
    (net (code "93") (name "unconnected-(U$15-MTMS-Pad47)") (class "Default")
      (node (ref "U$15") (pin "47") (pinfunction "MTMS_47") (pintype "bidirectional"))
    )
    (net (code "94") (name "unconnected-(U$15-SPICS1-Pad29)") (class "Default")
      (node (ref "U$15") (pin "29") (pinfunction "SPICS1_29") (pintype "bidirectional"))
    )
    (net (code "95") (name "unconnected-(U$15-XTAL_32K_N-Pad22)") (class "Default")
      (node (ref "U$15") (pin "22") (pinfunction "XTAL_32K_N_22") (pintype "bidirectional"))
    )
    (net (code "96") (name "unconnected-(U$15-XTAL_32K_P-Pad21)") (class "Default")
      (node (ref "U$15") (pin "21") (pinfunction "XTAL_32K_P_21") (pintype "bidirectional"))
    )
    (net (code "97") (name "unconnected-(U4-PadDO)") (class "Default")
      (node (ref "U4") (pin "DO") (pinfunction "DO_DO") (pintype "bidirectional"))
    )
  )
)
